# powser_v1.net
KiCad netlist of a schematic drawn in EAGLE
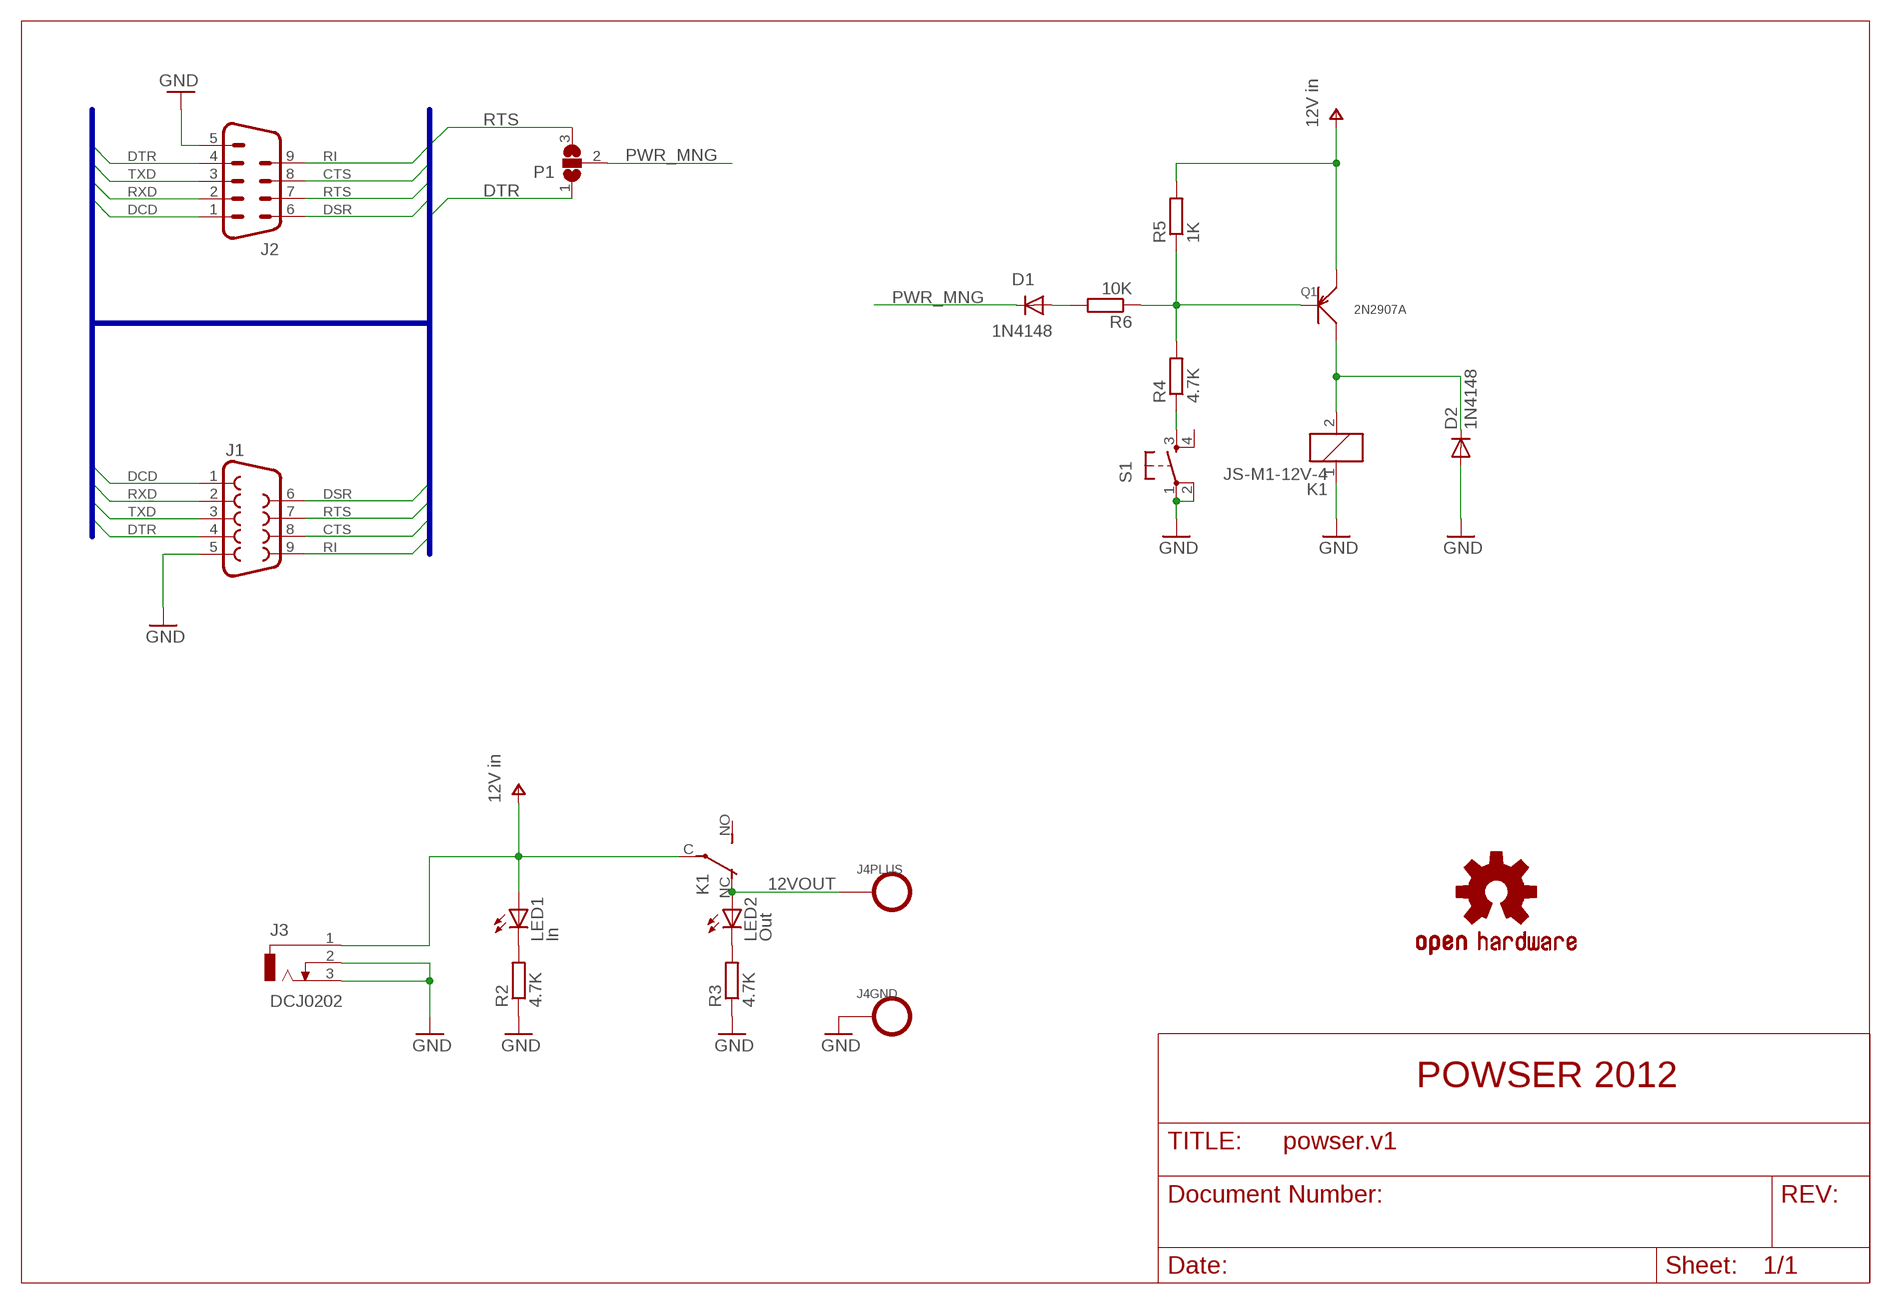
[diagram p0: schematic, sheet 1]

(export (version "E")
  (design (tool "Eeschema 10.0.6"))
  (components
    (comp (ref "D1")
      (value "1N4148")
      (footprint "eagle-import:SOD123")
      (libsource (lib "eagle-import") (part "DIODE-SOD123"))
    )
    (comp (ref "D2")
      (value "1N4148")
      (footprint "eagle-import:SOD123")
      (libsource (lib "eagle-import") (part "DIODE-SOD123"))
    )
    (comp (ref "J1")
      (value "F09D")
      (footprint "eagle-import:F09D")
      (libsource (lib "eagle-import") (part "F09D"))
    )
    (comp (ref "J2")
      (value "M09D")
      (footprint "eagle-import:M09D")
      (libsource (lib "eagle-import") (part "M09D"))
    )
    (comp (ref "J3")
      (value "DCJ0202")
      (footprint "eagle-import:DCJ0202")
      (libsource (lib "eagle-import") (part "DCJ0202"))
    )
    (comp (ref "J4")
      (value "POWER-OUT")
      (footprint "eagle-import:FLEX-POWER")
      (libsource (lib "eagle-import") (part "POWER-OUT"))
    )
    (comp (ref "K1")
      (value "JS-M1-12V-4")
      (footprint "eagle-import:SRD")
      (fields
        (field (name "MPN") "JSM1-12V-4")
        (field (name "MPN_1") "JSM1-12V-4")
        (field (name "OC_FARNELL") "910338")
        (field (name "OC_NEWARK") "13P4552")
      )
      (libsource (lib "eagle-import") (part "JS-M1-12V-4"))
    )
    (comp (ref "LED1")
      (value "In")
      (footprint "eagle-import:CHIPLED_0805")
      (libsource (lib "eagle-import") (part "LEDCHIPLED_0805"))
    )
    (comp (ref "LED2")
      (value "Out")
      (footprint "eagle-import:CHIPLED_0805")
      (libsource (lib "eagle-import") (part "LEDCHIPLED_0805"))
    )
    (comp (ref "P1")
      (value "PAD-SOLDERJUMPER-2WAYT")
      (footprint "eagle-import:3P-SMD-4.8X2")
      (libsource (lib "eagle-import") (part "PAD-SOLDERJUMPER-2WAYT"))
    )
    (comp (ref "Q1")
      (value "2N2907A")
      (footprint "eagle-import:TO-92-TRIANGLE")
      (libsource (lib "eagle-import") (part "TRANSISTOR-PNP-TO-92"))
    )
    (comp (ref "R2")
      (value "4.7K")
      (footprint "eagle-import:M0805")
      (libsource (lib "eagle-import") (part "R-EU_M0805"))
    )
    (comp (ref "R3")
      (value "4.7K")
      (footprint "eagle-import:M0805")
      (libsource (lib "eagle-import") (part "R-EU_M0805"))
    )
    (comp (ref "R4")
      (value "4.7K")
      (footprint "eagle-import:M0805")
      (libsource (lib "eagle-import") (part "R-EU_M0805"))
    )
    (comp (ref "R5")
      (value "1K")
      (footprint "eagle-import:M0805")
      (libsource (lib "eagle-import") (part "R-EU_M0805"))
    )
    (comp (ref "R6")
      (value "10K")
      (footprint "eagle-import:M0805")
      (libsource (lib "eagle-import") (part "R-EU_M0805"))
    )
    (comp (ref "S1")
      (value "TAC_SWITCHPTH")
      (footprint "eagle-import:TACTILE-PTH")
      (libsource (lib "eagle-import") (part "TAC_SWITCHPTH"))
    )
    (comp (ref "U$1")
      (value "OSHW-LOGOL")
      (footprint "eagle-import:OSHW-LOGO-L")
      (libsource (lib "eagle-import") (part "OSHW-LOGOL"))
    )
  )
  (nets
    (net (code "1") (name "/12VOUT") (class "Default")
      (node (ref "J4") (pin "1") (pinfunction "P$1_1") (pintype "bidirectional"))
      (node (ref "K1") (pin "NC") (pinfunction "O_NC") (pintype "passive"))
      (node (ref "LED2") (pin "A") (pinfunction "A_A") (pintype "passive"))
    )
    (net (code "2") (name "/CTS") (class "Default")
      (node (ref "J1") (pin "8") (pinfunction "8_8") (pintype "passive"))
      (node (ref "J2") (pin "8") (pinfunction "8_8") (pintype "passive"))
    )
    (net (code "3") (name "/DCD") (class "Default")
      (node (ref "J1") (pin "1") (pinfunction "1_1") (pintype "passive"))
      (node (ref "J2") (pin "1") (pinfunction "1_1") (pintype "passive"))
    )
    (net (code "4") (name "/DSR") (class "Default")
      (node (ref "J1") (pin "6") (pinfunction "6_6") (pintype "passive"))
      (node (ref "J2") (pin "6") (pinfunction "6_6") (pintype "passive"))
    )
    (net (code "5") (name "/DTR") (class "Default")
      (node (ref "J1") (pin "4") (pinfunction "4_4") (pintype "passive"))
      (node (ref "J2") (pin "4") (pinfunction "4_4") (pintype "passive"))
      (node (ref "P1") (pin "1") (pinfunction "1_1") (pintype "passive"))
    )
    (net (code "6") (name "/PWR_MNG") (class "Default")
      (node (ref "D1") (pin "C") (pinfunction "C_C") (pintype "passive"))
      (node (ref "P1") (pin "2") (pinfunction "2_2") (pintype "passive"))
    )
    (net (code "7") (name "/RI") (class "Default")
      (node (ref "J1") (pin "9") (pinfunction "9_9") (pintype "passive"))
      (node (ref "J2") (pin "9") (pinfunction "9_9") (pintype "passive"))
    )
    (net (code "8") (name "/RTS") (class "Default")
      (node (ref "J1") (pin "7") (pinfunction "7_7") (pintype "passive"))
      (node (ref "J2") (pin "7") (pinfunction "7_7") (pintype "passive"))
      (node (ref "P1") (pin "3") (pinfunction "3_3") (pintype "passive"))
    )
    (net (code "9") (name "/RXD") (class "Default")
      (node (ref "J1") (pin "2") (pinfunction "2_2") (pintype "passive"))
      (node (ref "J2") (pin "2") (pinfunction "2_2") (pintype "passive"))
    )
    (net (code "10") (name "/TXD") (class "Default")
      (node (ref "J1") (pin "3") (pinfunction "3_3") (pintype "passive"))
      (node (ref "J2") (pin "3") (pinfunction "3_3") (pintype "passive"))
    )
    (net (code "11") (name "12V in") (class "Default")
      (node (ref "J3") (pin "1") (pinfunction "1_1") (pintype "passive"))
      (node (ref "K1") (pin "C") (pinfunction "P_C") (pintype "passive"))
      (node (ref "LED1") (pin "A") (pinfunction "A_A") (pintype "passive"))
      (node (ref "Q1") (pin "1") (pinfunction "E_1") (pintype "passive"))
      (node (ref "R5") (pin "2") (pinfunction "2_2") (pintype "passive"))
    )
    (net (code "12") (name "GND") (class "Default")
      (node (ref "D2") (pin "A") (pinfunction "A_A") (pintype "passive"))
      (node (ref "J1") (pin "5") (pinfunction "5_5") (pintype "passive"))
      (node (ref "J2") (pin "5") (pinfunction "5_5") (pintype "passive"))
      (node (ref "J3") (pin "2") (pinfunction "2_2") (pintype "passive"))
      (node (ref "J3") (pin "3") (pinfunction "3_3") (pintype "passive"))
      (node (ref "J4") (pin "2") (pinfunction "P$1_2") (pintype "bidirectional"))
      (node (ref "K1") (pin "1") (pinfunction "1_1") (pintype "passive"))
      (node (ref "R2") (pin "1") (pinfunction "1_1") (pintype "passive"))
      (node (ref "R3") (pin "1") (pinfunction "1_1") (pintype "passive"))
      (node (ref "S1") (pin "1") (pinfunction "1_1") (pintype "passive"))
      (node (ref "S1") (pin "2") (pinfunction "2_2") (pintype "passive"))
    )
    (net (code "13") (name "Net-(D1-PadA)") (class "Default")
      (node (ref "D1") (pin "A") (pinfunction "A_A") (pintype "passive"))
      (node (ref "R6") (pin "2") (pinfunction "2_2") (pintype "passive"))
    )
    (net (code "14") (name "Net-(LED1-PadC)") (class "Default")
      (node (ref "LED1") (pin "C") (pinfunction "C_C") (pintype "passive"))
      (node (ref "R2") (pin "2") (pinfunction "2_2") (pintype "passive"))
    )
    (net (code "15") (name "Net-(LED2-PadC)") (class "Default")
      (node (ref "LED2") (pin "C") (pinfunction "C_C") (pintype "passive"))
      (node (ref "R3") (pin "2") (pinfunction "2_2") (pintype "passive"))
    )
    (net (code "16") (name "Net-(Q1-B)") (class "Default")
      (node (ref "Q1") (pin "2") (pinfunction "B_2") (pintype "passive"))
      (node (ref "R4") (pin "2") (pinfunction "2_2") (pintype "passive"))
      (node (ref "R5") (pin "1") (pinfunction "1_1") (pintype "passive"))
      (node (ref "R6") (pin "1") (pinfunction "1_1") (pintype "passive"))
    )
    (net (code "17") (name "Net-(Q1-C)") (class "Default")
      (node (ref "D2") (pin "C") (pinfunction "C_C") (pintype "passive"))
      (node (ref "K1") (pin "2") (pinfunction "2_2") (pintype "passive"))
      (node (ref "Q1") (pin "3") (pinfunction "C_3") (pintype "passive"))
    )
    (net (code "18") (name "Net-(R4-Pad1)") (class "Default")
      (node (ref "R4") (pin "1") (pinfunction "1_1") (pintype "passive"))
      (node (ref "S1") (pin "3") (pinfunction "3_3") (pintype "passive"))
    )
    (net (code "19") (name "unconnected-(K1B-S-PadNO)") (class "Default")
      (node (ref "K1") (pin "NO") (pinfunction "S_NO") (pintype "passive"))
    )
    (net (code "20") (name "unconnected-(S1-Pad4)") (class "Default")
      (node (ref "S1") (pin "4") (pinfunction "4_4") (pintype "passive"))
    )
  )
)
